# untitled.net
KiCad netlist of a schematic drawn in EAGLE
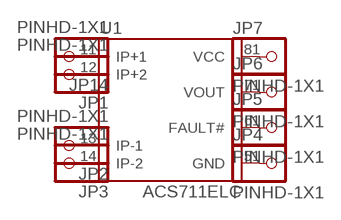
[diagram p0: schematic, sheet 1]

(export (version "E")
  (design (tool "Eeschema 10.0.6"))
  (components
    (comp (ref "JP1")
      (value "PINHD-1X1")
      (footprint "eagle-import:1X01")
      (libsource (lib "eagle-import") (part "PINHD-1X1"))
    )
    (comp (ref "JP2")
      (value "PINHD-1X1")
      (footprint "eagle-import:1X01")
      (libsource (lib "eagle-import") (part "PINHD-1X1"))
    )
    (comp (ref "JP3")
      (value "PINHD-1X1")
      (footprint "eagle-import:1X01")
      (libsource (lib "eagle-import") (part "PINHD-1X1"))
    )
    (comp (ref "JP4")
      (value "PINHD-1X1")
      (footprint "eagle-import:1X01")
      (libsource (lib "eagle-import") (part "PINHD-1X1"))
    )
    (comp (ref "JP5")
      (value "PINHD-1X1")
      (footprint "eagle-import:1X01")
      (libsource (lib "eagle-import") (part "PINHD-1X1"))
    )
    (comp (ref "JP6")
      (value "PINHD-1X1")
      (footprint "eagle-import:1X01")
      (libsource (lib "eagle-import") (part "PINHD-1X1"))
    )
    (comp (ref "JP7")
      (value "PINHD-1X1")
      (footprint "eagle-import:1X01")
      (libsource (lib "eagle-import") (part "PINHD-1X1"))
    )
    (comp (ref "JP14")
      (value "PINHD-1X1")
      (footprint "eagle-import:1X01")
      (libsource (lib "eagle-import") (part "PINHD-1X1"))
    )
    (comp (ref "U1")
      (value "ACS711ELC")
      (footprint "eagle-import:SOIC8")
      (libsource (lib "eagle-import") (part "ACS711ELC"))
    )
  )
  (nets
    (net (code "1") (name "Net-(U1-FAULT#)") (class "Default")
      (node (ref "JP5") (pin "1") (pinfunction "1_1") (pintype "passive"))
      (node (ref "U1") (pin "6") (pinfunction "FAULT#_6") (pintype "bidirectional"))
    )
    (net (code "2") (name "Net-(U1-GND)") (class "Default")
      (node (ref "JP4") (pin "1") (pinfunction "1_1") (pintype "passive"))
      (node (ref "U1") (pin "5") (pinfunction "GND_5") (pintype "bidirectional"))
    )
    (net (code "3") (name "Net-(U1-IP+1)") (class "Default")
      (node (ref "JP14") (pin "1") (pinfunction "1_1") (pintype "passive"))
      (node (ref "U1") (pin "1") (pinfunction "IP+1_1") (pintype "bidirectional"))
    )
    (net (code "4") (name "Net-(U1-IP+2)") (class "Default")
      (node (ref "JP1") (pin "1") (pinfunction "1_1") (pintype "passive"))
      (node (ref "U1") (pin "2") (pinfunction "IP+2_2") (pintype "bidirectional"))
    )
    (net (code "5") (name "Net-(U1-IP-1)") (class "Default")
      (node (ref "JP2") (pin "1") (pinfunction "1_1") (pintype "passive"))
      (node (ref "U1") (pin "3") (pinfunction "IP-1_3") (pintype "bidirectional"))
    )
    (net (code "6") (name "Net-(U1-IP-2)") (class "Default")
      (node (ref "JP3") (pin "1") (pinfunction "1_1") (pintype "passive"))
      (node (ref "U1") (pin "4") (pinfunction "IP-2_4") (pintype "bidirectional"))
    )
    (net (code "7") (name "Net-(U1-VCC)") (class "Default")
      (node (ref "JP7") (pin "1") (pinfunction "1_1") (pintype "passive"))
      (node (ref "U1") (pin "8") (pinfunction "VCC_8") (pintype "bidirectional"))
    )
    (net (code "8") (name "Net-(U1-VOUT)") (class "Default")
      (node (ref "JP6") (pin "1") (pinfunction "1_1") (pintype "passive"))
      (node (ref "U1") (pin "7") (pinfunction "VOUT_7") (pintype "bidirectional"))
    )
  )
)
